# design.net
KiCad netlist of a schematic drawn in Altium Designer
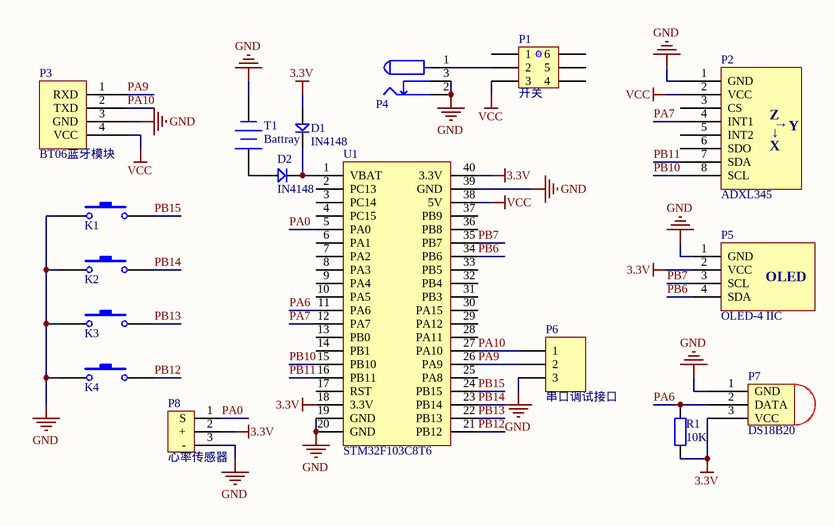
[diagram p0: 电路图.SchDoc]

(export (version "E")
  (design (tool "Eeschema 10.0.6"))
  (components
    (comp (ref "D1")
      (value "IN4148")
      (footprint "IN4148")
      (description "Diode")
      (libsource (lib "Component") (part "Diode"))
    )
    (comp (ref "D2")
      (value "IN4148")
      (footprint "IN4148")
      (description "Diode")
      (libsource (lib "Component") (part "Diode"))
    )
    (comp (ref "K1") (value "KEY") (footprint "KEY") (libsource (lib "Component") (part "KEY")))
    (comp (ref "K2") (value "KEY") (footprint "KEY") (libsource (lib "Component") (part "KEY")))
    (comp (ref "K3") (value "KEY") (footprint "KEY") (libsource (lib "Component") (part "KEY")))
    (comp (ref "K4") (value "KEY") (footprint "KEY") (libsource (lib "Component") (part "KEY")))
    (comp (ref "P1") (value "开关") (footprint "Switch") (libsource (lib "Component") (part "Switch")))
    (comp (ref "P2")
      (value "ADXL345")
      (footprint "MPU6050")
      (description "8PIN")
      (libsource (lib "Moudle") (part "ADXL345"))
    )
    (comp (ref "P3")
      (value "BT06蓝牙模块")
      (footprint "BT06")
      (description "4PIN")
      (libsource (lib "Moudle") (part "BT06"))
    )
    (comp (ref "P4")
      (value "电源插座")
      (footprint "DC 3.5-1.3mm")
      (description "3PIN")
      (libsource (lib "Component") (part "POWER"))
    )
    (comp (ref "P5")
      (value "OLED-4 IIC")
      (description "4PIN")
      (libsource (lib "Component") (part "OLED-4 IIC"))
    )
    (comp (ref "P6")
      (value "串口调试接口")
      (footprint "HDR1X3")
      (description "Header, 3-Pin")
      (fields (field (name "PUBLISHER") "Altium Limited"))
      (libsource (lib "Miscellaneous Connectors") (part "Header 3"))
    )
    (comp (ref "P7") (value "DS18B20") (footprint "DS18B20") (libsource (lib "Component") (part "DS18B20")))
    (comp (ref "P8") (value "心率传感器") (footprint "Header3x1") (libsource (lib "Component") (part "Pulse")))
    (comp (ref "R1")
      (value "10K")
      (footprint "RES-4")
      (description "RES")
      (libsource (lib "Component") (part "RES"))
    )
    (comp (ref "T1")
      (value "Battray")
      (footprint "Battray-1220")
      (libsource (lib "Component") (part "Battray"))
    )
    (comp (ref "U1")
      (value "STM32F103C8T6")
      (footprint "STM32F103C8T6 #MK48")
      (description "40PIN")
      (libsource (lib "Moudle") (part "STM32F103C8T6  #MK480"))
    )
  )
  (nets
    (net (code "1") (name "/PA0") (class "Default")
      (node (ref "P8") (pin "1") (pinfunction "S_1") (pintype "passive"))
      (node (ref "U1") (pin "5") (pinfunction "PA0_5") (pintype "passive"))
    )
    (net (code "2") (name "/PA6") (class "Default")
      (node (ref "P7") (pin "2") (pinfunction "DATA_2") (pintype "passive"))
      (node (ref "R1") (pin "2") (pinfunction "2_2") (pintype "passive"))
      (node (ref "U1") (pin "11") (pinfunction "PA6_11") (pintype "passive"))
    )
    (net (code "3") (name "/PA7") (class "Default")
      (node (ref "P2") (pin "4") (pinfunction "INT1_4") (pintype "passive"))
      (node (ref "U1") (pin "12") (pinfunction "PA7_12") (pintype "passive"))
    )
    (net (code "4") (name "/PA9") (class "Default")
      (node (ref "P3") (pin "1") (pinfunction "RXD_1") (pintype "passive"))
      (node (ref "P6") (pin "2") (pinfunction "2_2") (pintype "passive"))
      (node (ref "U1") (pin "26") (pinfunction "PA9_26") (pintype "passive"))
    )
    (net (code "5") (name "/PA10") (class "Default")
      (node (ref "P3") (pin "2") (pinfunction "TXD_2") (pintype "passive"))
      (node (ref "P6") (pin "1") (pinfunction "1_1") (pintype "passive"))
      (node (ref "U1") (pin "27") (pinfunction "PA10_27") (pintype "passive"))
    )
    (net (code "6") (name "/PB6") (class "Default")
      (node (ref "P5") (pin "4") (pinfunction "SDA_4") (pintype "passive"))
      (node (ref "U1") (pin "34") (pinfunction "PB6_34") (pintype "passive"))
    )
    (net (code "7") (name "/PB7") (class "Default")
      (node (ref "P5") (pin "3") (pinfunction "SCL_3") (pintype "passive"))
      (node (ref "U1") (pin "35") (pinfunction "PB7_35") (pintype "passive"))
    )
    (net (code "8") (name "/PB10") (class "Default")
      (node (ref "P2") (pin "8") (pinfunction "SCL_8") (pintype "passive"))
      (node (ref "U1") (pin "15") (pinfunction "PB10_15") (pintype "passive"))
    )
    (net (code "9") (name "/PB11") (class "Default")
      (node (ref "P2") (pin "7") (pinfunction "SDA_7") (pintype "passive"))
      (node (ref "U1") (pin "16") (pinfunction "PB11_16") (pintype "passive"))
    )
    (net (code "10") (name "/PB12") (class "Default")
      (node (ref "K4") (pin "2") (pinfunction "2_2") (pintype "passive"))
      (node (ref "U1") (pin "21") (pinfunction "PB12_21") (pintype "passive"))
    )
    (net (code "11") (name "/PB13") (class "Default")
      (node (ref "K3") (pin "2") (pinfunction "2_2") (pintype "passive"))
      (node (ref "U1") (pin "22") (pinfunction "PB13_22") (pintype "passive"))
    )
    (net (code "12") (name "/PB14") (class "Default")
      (node (ref "K2") (pin "2") (pinfunction "2_2") (pintype "passive"))
      (node (ref "U1") (pin "23") (pinfunction "PB14_23") (pintype "passive"))
    )
    (net (code "13") (name "/PB15") (class "Default")
      (node (ref "K1") (pin "2") (pinfunction "2_2") (pintype "passive"))
      (node (ref "U1") (pin "24") (pinfunction "PB15_24") (pintype "passive"))
    )
    (net (code "14") (name "3.3V") (class "Default")
      (node (ref "D1") (pin "1") (pintype "passive"))
      (node (ref "P5") (pin "2") (pinfunction "VCC_2") (pintype "passive"))
      (node (ref "P7") (pin "3") (pinfunction "VCC_3") (pintype "passive"))
      (node (ref "P8") (pin "2") (pinfunction "+_2") (pintype "passive"))
      (node (ref "R1") (pin "1") (pinfunction "1_1") (pintype "passive"))
      (node (ref "U1") (pin "18") (pinfunction "3.3V_18") (pintype "passive"))
      (node (ref "U1") (pin "40") (pinfunction "3.3V_40") (pintype "passive"))
    )
    (net (code "15") (name "GND") (class "Default")
      (node (ref "K1") (pin "1") (pinfunction "1_1") (pintype "passive"))
      (node (ref "K2") (pin "1") (pinfunction "1_1") (pintype "passive"))
      (node (ref "K3") (pin "1") (pinfunction "1_1") (pintype "passive"))
      (node (ref "K4") (pin "1") (pinfunction "1_1") (pintype "passive"))
      (node (ref "P2") (pin "1") (pinfunction "GND_1") (pintype "passive"))
      (node (ref "P3") (pin "3") (pinfunction "GND_3") (pintype "passive"))
      (node (ref "P4") (pin "2") (pintype "passive"))
      (node (ref "P4") (pin "3") (pintype "passive"))
      (node (ref "P5") (pin "1") (pinfunction "GND_1") (pintype "passive"))
      (node (ref "P6") (pin "3") (pinfunction "3_3") (pintype "passive"))
      (node (ref "P7") (pin "1") (pinfunction "GND_1") (pintype "passive"))
      (node (ref "P8") (pin "3") (pinfunction "-_3") (pintype "passive"))
      (node (ref "T1") (pin "2") (pinfunction "-_2") (pintype "passive"))
      (node (ref "U1") (pin "19") (pinfunction "GND_19") (pintype "passive"))
      (node (ref "U1") (pin "20") (pinfunction "GND_20") (pintype "passive"))
      (node (ref "U1") (pin "39") (pinfunction "GND_39") (pintype "passive"))
    )
    (net (code "16") (name "Net-(P1-Pad2)") (class "Default")
      (node (ref "P1") (pin "2") (pinfunction "2_2") (pintype "passive"))
      (node (ref "P4") (pin "1") (pintype "passive"))
    )
    (net (code "17") (name "Net-(T1-+)") (class "Default")
      (node (ref "D2") (pin "1") (pintype "passive"))
      (node (ref "T1") (pin "1") (pinfunction "+_1") (pintype "passive"))
    )
    (net (code "18") (name "Net-(U1-VBAT)") (class "Default")
      (node (ref "D1") (pin "2") (pintype "passive"))
      (node (ref "D2") (pin "2") (pintype "passive"))
      (node (ref "U1") (pin "1") (pinfunction "VBAT_1") (pintype "passive"))
    )
    (net (code "19") (name "VCC") (class "Default")
      (node (ref "P1") (pin "3") (pinfunction "3_3") (pintype "passive"))
      (node (ref "P2") (pin "2") (pinfunction "VCC_2") (pintype "passive"))
      (node (ref "P3") (pin "4") (pinfunction "VCC_4") (pintype "passive"))
      (node (ref "U1") (pin "38") (pinfunction "5V_38") (pintype "passive"))
    )
    (net (code "20") (name "unconnected-(P1-Pad1)") (class "Default")
      (node (ref "P1") (pin "1") (pinfunction "1_1") (pintype "passive"))
    )
    (net (code "21") (name "unconnected-(P1-Pad4)") (class "Default")
      (node (ref "P1") (pin "4") (pinfunction "4_4") (pintype "passive"))
    )
    (net (code "22") (name "unconnected-(P1-Pad5)") (class "Default")
      (node (ref "P1") (pin "5") (pinfunction "5_5") (pintype "passive"))
    )
    (net (code "23") (name "unconnected-(P1-Pad6)") (class "Default")
      (node (ref "P1") (pin "6") (pinfunction "6_6") (pintype "passive"))
    )
    (net (code "24") (name "unconnected-(P2-CS-Pad3)") (class "Default")
      (node (ref "P2") (pin "3") (pinfunction "CS_3") (pintype "passive"))
    )
    (net (code "25") (name "unconnected-(P2-INT2-Pad5)") (class "Default")
      (node (ref "P2") (pin "5") (pinfunction "INT2_5") (pintype "passive"))
    )
    (net (code "26") (name "unconnected-(P2-SDO-Pad6)") (class "Default")
      (node (ref "P2") (pin "6") (pinfunction "SDO_6") (pintype "passive"))
    )
    (net (code "27") (name "unconnected-(U1-PA1-Pad6)") (class "Default")
      (node (ref "U1") (pin "6") (pinfunction "PA1_6") (pintype "passive"))
    )
    (net (code "28") (name "unconnected-(U1-PA2-Pad7)") (class "Default")
      (node (ref "U1") (pin "7") (pinfunction "PA2_7") (pintype "passive"))
    )
    (net (code "29") (name "unconnected-(U1-PA3-Pad8)") (class "Default")
      (node (ref "U1") (pin "8") (pinfunction "PA3_8") (pintype "passive"))
    )
    (net (code "30") (name "unconnected-(U1-PA4-Pad9)") (class "Default")
      (node (ref "U1") (pin "9") (pinfunction "PA4_9") (pintype "passive"))
    )
    (net (code "31") (name "unconnected-(U1-PA5-Pad10)") (class "Default")
      (node (ref "U1") (pin "10") (pinfunction "PA5_10") (pintype "passive"))
    )
    (net (code "32") (name "unconnected-(U1-PA8-Pad25)") (class "Default")
      (node (ref "U1") (pin "25") (pinfunction "PA8_25") (pintype "passive"))
    )
    (net (code "33") (name "unconnected-(U1-PA11-Pad28)") (class "Default")
      (node (ref "U1") (pin "28") (pinfunction "PA11_28") (pintype "passive"))
    )
    (net (code "34") (name "unconnected-(U1-PA12-Pad29)") (class "Default")
      (node (ref "U1") (pin "29") (pinfunction "PA12_29") (pintype "passive"))
    )
    (net (code "35") (name "unconnected-(U1-PA15-Pad30)") (class "Default")
      (node (ref "U1") (pin "30") (pinfunction "PA15_30") (pintype "passive"))
    )
    (net (code "36") (name "unconnected-(U1-PB0-Pad13)") (class "Default")
      (node (ref "U1") (pin "13") (pinfunction "PB0_13") (pintype "passive"))
    )
    (net (code "37") (name "unconnected-(U1-PB1-Pad14)") (class "Default")
      (node (ref "U1") (pin "14") (pinfunction "PB1_14") (pintype "passive"))
    )
    (net (code "38") (name "unconnected-(U1-PB3-Pad31)") (class "Default")
      (node (ref "U1") (pin "31") (pinfunction "PB3_31") (pintype "passive"))
    )
    (net (code "39") (name "unconnected-(U1-PB4-Pad32)") (class "Default")
      (node (ref "U1") (pin "32") (pinfunction "PB4_32") (pintype "passive"))
    )
    (net (code "40") (name "unconnected-(U1-PB5-Pad33)") (class "Default")
      (node (ref "U1") (pin "33") (pinfunction "PB5_33") (pintype "passive"))
    )
    (net (code "41") (name "unconnected-(U1-PB8-Pad36)") (class "Default")
      (node (ref "U1") (pin "36") (pinfunction "PB8_36") (pintype "passive"))
    )
    (net (code "42") (name "unconnected-(U1-PB9-Pad37)") (class "Default")
      (node (ref "U1") (pin "37") (pinfunction "PB9_37") (pintype "passive"))
    )
    (net (code "43") (name "unconnected-(U1-PC13-Pad2)") (class "Default")
      (node (ref "U1") (pin "2") (pinfunction "PC13_2") (pintype "passive"))
    )
    (net (code "44") (name "unconnected-(U1-PC14-Pad3)") (class "Default")
      (node (ref "U1") (pin "3") (pinfunction "PC14_3") (pintype "passive"))
    )
    (net (code "45") (name "unconnected-(U1-PC15-Pad4)") (class "Default")
      (node (ref "U1") (pin "4") (pinfunction "PC15_4") (pintype "passive"))
    )
    (net (code "46") (name "unconnected-(U1-RST-Pad17)") (class "Default")
      (node (ref "U1") (pin "17") (pinfunction "RST_17") (pintype "passive"))
    )
  )
)
